# GTM_UARTconnector.net
KiCad netlist of a schematic drawn in Altium Designer
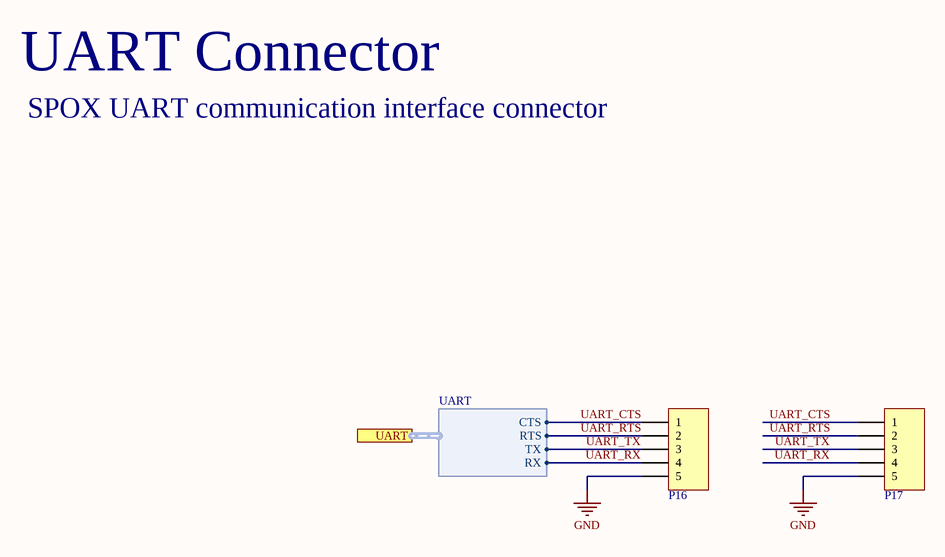
[diagram p0: GTM_UARTconnector.SchDoc]

(export (version "E")
  (design (tool "Eeschema 10.0.6"))
  (components
    (comp (ref "P16")
      (value "HDR1X5")
      (footprint "Molex SPOX Horizontal 5 Circuits")
      (description "Header, 5-Pin")
      (fields (field (name "PUBLISHER") "Altium Limited"))
      (libsource (lib "Library_Altium_KNR") (part "HDR1X5"))
    )
    (comp (ref "P17")
      (value "HDR1X5")
      (footprint "Molex SPOX Horizontal 5 Circuits")
      (description "Doubled Connector")
      (fields (field (name "PUBLISHER") "Altium Limited"))
      (libsource (lib "Library_Altium_KNR") (part "HDR1X5"))
    )
  )
  (nets
    (net (code "2") (name "/UART_CTS") (class "Default")
      (node (ref "P16") (pin "1") (pinfunction "1_1") (pintype "passive"))
      (node (ref "P17") (pin "1") (pinfunction "1_1") (pintype "passive"))
    )
    (net (code "3") (name "/UART_RTS") (class "Default")
      (node (ref "P16") (pin "2") (pinfunction "2_2") (pintype "passive"))
      (node (ref "P17") (pin "2") (pinfunction "2_2") (pintype "passive"))
    )
    (net (code "4") (name "/UART_RX") (class "Default")
      (node (ref "P16") (pin "4") (pinfunction "4_4") (pintype "passive"))
      (node (ref "P17") (pin "4") (pinfunction "4_4") (pintype "passive"))
    )
    (net (code "5") (name "/UART_TX") (class "Default")
      (node (ref "P16") (pin "3") (pinfunction "3_3") (pintype "passive"))
      (node (ref "P17") (pin "3") (pinfunction "3_3") (pintype "passive"))
    )
    (net (code "7") (name "GND") (class "Default")
      (node (ref "P16") (pin "5") (pinfunction "5_5") (pintype "passive"))
      (node (ref "P17") (pin "5") (pinfunction "5_5") (pintype "passive"))
    )
  )
)
